# HDMI_To_MIPI_PHY.net
KiCad netlist of a schematic drawn in Altium Designer
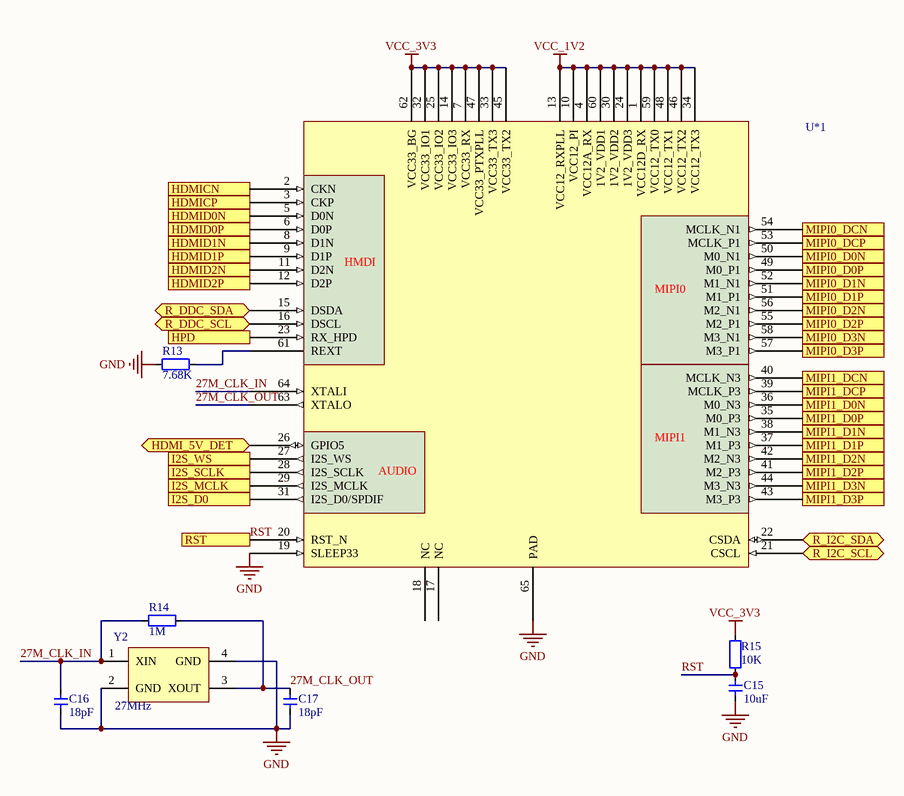
[diagram p0: HDMI_To_MIPI_PHY.SchDoc]

(export (version "E")
  (design (tool "Eeschema 10.0.6"))
  (components
    (comp (ref "C15")
      (value "10uF")
      (footprint "CAP_0402")
      (description "Capacitor")
      (libsource (lib "MyPcbLib") (part "电容-0402"))
    )
    (comp (ref "C16")
      (value "18pF")
      (footprint "CAP_0402")
      (description "Capacitor")
      (libsource (lib "MyPcbLib") (part "电容-0402"))
    )
    (comp (ref "C17")
      (value "18pF")
      (footprint "CAP_0402")
      (description "Capacitor")
      (libsource (lib "MyPcbLib") (part "电容-0402"))
    )
    (comp (ref "R13")
      (value "7.68K")
      (footprint "RES_0402")
      (description "Resistor")
      (libsource (lib "MyPcbLib") (part "电阻-0402"))
    )
    (comp (ref "R14")
      (value "1M")
      (footprint "RES_0402")
      (description "Resistor")
      (libsource (lib "MyPcbLib") (part "电阻-0402"))
    )
    (comp (ref "R15")
      (value "10K")
      (footprint "RES_0402")
      (description "Resistor")
      (libsource (lib "") (part "电阻-0402_1"))
    )
    (comp (ref "U*1")
      (value "LT6911C")
      (footprint "QFN-64-0.4mm")
      (description "HDMI to MIPI PHY")
      (libsource (lib "mLib") (part "LT6911C"))
    )
    (comp (ref "Y2")
      (value "27MHz")
      (footprint "晶振2520")
      (description "2520无源")
      (fields (field (name "MF") "ECS International") (field (name "MP") "ECS-3225S30-240-EN-TR"))
      (libsource (lib "MyPcbLib") (part "晶振-4Pin-无源"))
    )
  )
  (nets
    (net (code "1") (name "/27M_CLK_IN") (class "Default")
      (node (ref "C16") (pin "2") (pinfunction "2_2") (pintype "passive"))
      (node (ref "R14") (pin "1") (pinfunction "1_1") (pintype "passive"))
      (node (ref "U*1") (pin "64") (pinfunction "XTALI_64") (pintype "input"))
      (node (ref "Y2") (pin "1") (pinfunction "XIN_1") (pintype "passive"))
    )
    (net (code "2") (name "/27M_CLK_OUT") (class "Default")
      (node (ref "C17") (pin "2") (pinfunction "2_2") (pintype "passive"))
      (node (ref "R14") (pin "2") (pinfunction "2_2") (pintype "passive"))
      (node (ref "U*1") (pin "63") (pinfunction "XTALO_63") (pintype "output"))
      (node (ref "Y2") (pin "3") (pinfunction "XOUT_3") (pintype "passive"))
    )
    (net (code "3") (name "/HDMICN") (class "Default")
      (node (ref "U*1") (pin "2") (pinfunction "CKN_2") (pintype "input"))
    )
    (net (code "4") (name "/HDMICP") (class "Default")
      (node (ref "U*1") (pin "3") (pinfunction "CKP_3") (pintype "input"))
    )
    (net (code "5") (name "/HDMID0N") (class "Default")
      (node (ref "U*1") (pin "5") (pinfunction "D0N_5") (pintype "input"))
    )
    (net (code "6") (name "/HDMID0P") (class "Default")
      (node (ref "U*1") (pin "6") (pinfunction "D0P_6") (pintype "input"))
    )
    (net (code "7") (name "/HDMID1N") (class "Default")
      (node (ref "U*1") (pin "8") (pinfunction "D1N_8") (pintype "input"))
    )
    (net (code "8") (name "/HDMID1P") (class "Default")
      (node (ref "U*1") (pin "9") (pinfunction "D1P_9") (pintype "input"))
    )
    (net (code "9") (name "/HDMID2N") (class "Default")
      (node (ref "U*1") (pin "11") (pinfunction "D2N_11") (pintype "input"))
    )
    (net (code "10") (name "/HDMID2P") (class "Default")
      (node (ref "U*1") (pin "12") (pinfunction "D2P_12") (pintype "input"))
    )
    (net (code "11") (name "/HDMI_5V_DET") (class "Default")
      (node (ref "U*1") (pin "26") (pinfunction "GPIO5_26") (pintype "bidirectional"))
    )
    (net (code "12") (name "/HPD") (class "Default")
      (node (ref "U*1") (pin "23") (pinfunction "RX_HPD_23") (pintype "input"))
    )
    (net (code "13") (name "/I2S_D0") (class "Default")
      (node (ref "U*1") (pin "31") (pinfunction "I2S_D0/SPDIF_31") (pintype "output"))
    )
    (net (code "14") (name "/I2S_MCLK") (class "Default")
      (node (ref "U*1") (pin "29") (pinfunction "I2S_MCLK_29") (pintype "output"))
    )
    (net (code "15") (name "/I2S_SCLK") (class "Default")
      (node (ref "U*1") (pin "28") (pinfunction "I2S_SCLK_28") (pintype "output"))
    )
    (net (code "16") (name "/I2S_WS") (class "Default")
      (node (ref "U*1") (pin "27") (pinfunction "I2S_WS_27") (pintype "output"))
    )
    (net (code "17") (name "/MIPI0_D0N") (class "Default")
      (node (ref "U*1") (pin "50") (pinfunction "M0_N1_50") (pintype "output"))
    )
    (net (code "18") (name "/MIPI0_D0P") (class "Default")
      (node (ref "U*1") (pin "49") (pinfunction "M0_P1_49") (pintype "output"))
    )
    (net (code "19") (name "/MIPI0_D1N") (class "Default")
      (node (ref "U*1") (pin "52") (pinfunction "M1_N1_52") (pintype "output"))
    )
    (net (code "20") (name "/MIPI0_D1P") (class "Default")
      (node (ref "U*1") (pin "51") (pinfunction "M1_P1_51") (pintype "output"))
    )
    (net (code "21") (name "/MIPI0_D2N") (class "Default")
      (node (ref "U*1") (pin "56") (pinfunction "M2_N1_56") (pintype "output"))
    )
    (net (code "22") (name "/MIPI0_D2P") (class "Default")
      (node (ref "U*1") (pin "55") (pinfunction "M2_P1_55") (pintype "output"))
    )
    (net (code "23") (name "/MIPI0_D3N") (class "Default")
      (node (ref "U*1") (pin "58") (pinfunction "M3_N1_58") (pintype "output"))
    )
    (net (code "24") (name "/MIPI0_D3P") (class "Default")
      (node (ref "U*1") (pin "57") (pinfunction "M3_P1_57") (pintype "output"))
    )
    (net (code "25") (name "/MIPI0_DCN") (class "Default")
      (node (ref "U*1") (pin "54") (pinfunction "MCLK_N1_54") (pintype "output"))
    )
    (net (code "26") (name "/MIPI0_DCP") (class "Default")
      (node (ref "U*1") (pin "53") (pinfunction "MCLK_P1_53") (pintype "output"))
    )
    (net (code "27") (name "/MIPI1_D0N") (class "Default")
      (node (ref "U*1") (pin "36") (pinfunction "M0_N3_36") (pintype "output"))
    )
    (net (code "28") (name "/MIPI1_D0P") (class "Default")
      (node (ref "U*1") (pin "35") (pinfunction "M0_P3_35") (pintype "output"))
    )
    (net (code "29") (name "/MIPI1_D1N") (class "Default")
      (node (ref "U*1") (pin "38") (pinfunction "M1_N3_38") (pintype "output"))
    )
    (net (code "30") (name "/MIPI1_D1P") (class "Default")
      (node (ref "U*1") (pin "37") (pinfunction "M1_P3_37") (pintype "output"))
    )
    (net (code "31") (name "/MIPI1_D2N") (class "Default")
      (node (ref "U*1") (pin "42") (pinfunction "M2_N3_42") (pintype "output"))
    )
    (net (code "32") (name "/MIPI1_D2P") (class "Default")
      (node (ref "U*1") (pin "41") (pinfunction "M2_P3_41") (pintype "output"))
    )
    (net (code "33") (name "/MIPI1_D3N") (class "Default")
      (node (ref "U*1") (pin "44") (pinfunction "M3_N3_44") (pintype "output"))
    )
    (net (code "34") (name "/MIPI1_D3P") (class "Default")
      (node (ref "U*1") (pin "43") (pinfunction "M3_P3_43") (pintype "output"))
    )
    (net (code "35") (name "/MIPI1_DCN") (class "Default")
      (node (ref "U*1") (pin "40") (pinfunction "MCLK_N3_40") (pintype "output"))
    )
    (net (code "36") (name "/MIPI1_DCP") (class "Default")
      (node (ref "U*1") (pin "39") (pinfunction "MCLK_P3_39") (pintype "output"))
    )
    (net (code "37") (name "/RST") (class "Default")
      (node (ref "C15") (pin "2") (pinfunction "2_2") (pintype "passive"))
      (node (ref "R15") (pin "1") (pinfunction "1_1") (pintype "passive"))
      (node (ref "U*1") (pin "20") (pinfunction "RST_N_20") (pintype "input"))
    )
    (net (code "38") (name "/R_DDC_SCL") (class "Default")
      (node (ref "U*1") (pin "16") (pinfunction "DSCL_16") (pintype "input"))
    )
    (net (code "39") (name "/R_DDC_SDA") (class "Default")
      (node (ref "U*1") (pin "15") (pinfunction "DSDA_15") (pintype "input"))
    )
    (net (code "40") (name "/R_I2C_SCL") (class "Default")
      (node (ref "U*1") (pin "21") (pinfunction "CSCL_21") (pintype "input"))
    )
    (net (code "41") (name "/R_I2C_SDA") (class "Default")
      (node (ref "U*1") (pin "22") (pinfunction "CSDA_22") (pintype "bidirectional"))
    )
    (net (code "42") (name "GND") (class "Default")
      (node (ref "C15") (pin "1") (pinfunction "1_1") (pintype "passive"))
      (node (ref "C16") (pin "1") (pinfunction "1_1") (pintype "passive"))
      (node (ref "C17") (pin "1") (pinfunction "1_1") (pintype "passive"))
      (node (ref "R13") (pin "1") (pinfunction "1_1") (pintype "passive"))
      (node (ref "U*1") (pin "19") (pinfunction "SLEEP33_19") (pintype "input"))
      (node (ref "U*1") (pin "65") (pinfunction "PAD_65") (pintype "power_in"))
      (node (ref "Y2") (pin "2") (pinfunction "GND_2") (pintype "passive"))
      (node (ref "Y2") (pin "4") (pinfunction "GND_4") (pintype "passive"))
    )
    (net (code "43") (name "Net-(U*1-REXT)") (class "Default")
      (node (ref "R13") (pin "2") (pinfunction "2_2") (pintype "passive"))
      (node (ref "U*1") (pin "61") (pinfunction "REXT_61") (pintype "passive"))
    )
    (net (code "44") (name "VCC_1V2") (class "Default")
      (node (ref "U*1") (pin "1") (pinfunction "VCC12D_RX_1") (pintype "power_in"))
      (node (ref "U*1") (pin "10") (pinfunction "VCC12_PI_10") (pintype "power_in"))
      (node (ref "U*1") (pin "13") (pinfunction "VCC12_RXPLL_13") (pintype "power_in"))
      (node (ref "U*1") (pin "24") (pinfunction "1V2_VDD3_24") (pintype "power_in"))
      (node (ref "U*1") (pin "30") (pinfunction "1V2_VDD2_30") (pintype "power_in"))
      (node (ref "U*1") (pin "34") (pinfunction "VCC12_TX3_34") (pintype "power_in"))
      (node (ref "U*1") (pin "4") (pinfunction "VCC12A_RX_4") (pintype "power_in"))
      (node (ref "U*1") (pin "46") (pinfunction "VCC12_TX2_46") (pintype "power_in"))
      (node (ref "U*1") (pin "48") (pinfunction "VCC12_TX1_48") (pintype "power_in"))
      (node (ref "U*1") (pin "59") (pinfunction "VCC12_TX0_59") (pintype "power_in"))
      (node (ref "U*1") (pin "60") (pinfunction "1V2_VDD1_60") (pintype "power_in"))
    )
    (net (code "45") (name "VCC_3V3") (class "Default")
      (node (ref "R15") (pin "2") (pinfunction "2_2") (pintype "passive"))
      (node (ref "U*1") (pin "14") (pinfunction "VCC33_IO3_14") (pintype "power_in"))
      (node (ref "U*1") (pin "25") (pinfunction "VCC33_IO2_25") (pintype "power_in"))
      (node (ref "U*1") (pin "32") (pinfunction "VCC33_IO1_32") (pintype "power_in"))
      (node (ref "U*1") (pin "33") (pinfunction "VCC33_TX3_33") (pintype "power_in"))
      (node (ref "U*1") (pin "45") (pinfunction "VCC33_TX2_45") (pintype "power_in"))
      (node (ref "U*1") (pin "47") (pinfunction "VCC33_PTXPLL_47") (pintype "power_in"))
      (node (ref "U*1") (pin "62") (pinfunction "VCC33_BG_62") (pintype "power_in"))
      (node (ref "U*1") (pin "7") (pinfunction "VCC33_RX_7") (pintype "power_in"))
    )
    (net (code "46") (name "unconnected-(U*1-NC-Pad17)") (class "Default")
      (node (ref "U*1") (pin "17") (pinfunction "NC_17") (pintype "tri_state"))
    )
    (net (code "47") (name "unconnected-(U*1-NC-Pad18)") (class "Default")
      (node (ref "U*1") (pin "18") (pinfunction "NC_18") (pintype "tri_state"))
    )
  )
)
